# Controlador_de_velocidad.net
KiCad netlist of a schematic drawn in Altium Designer
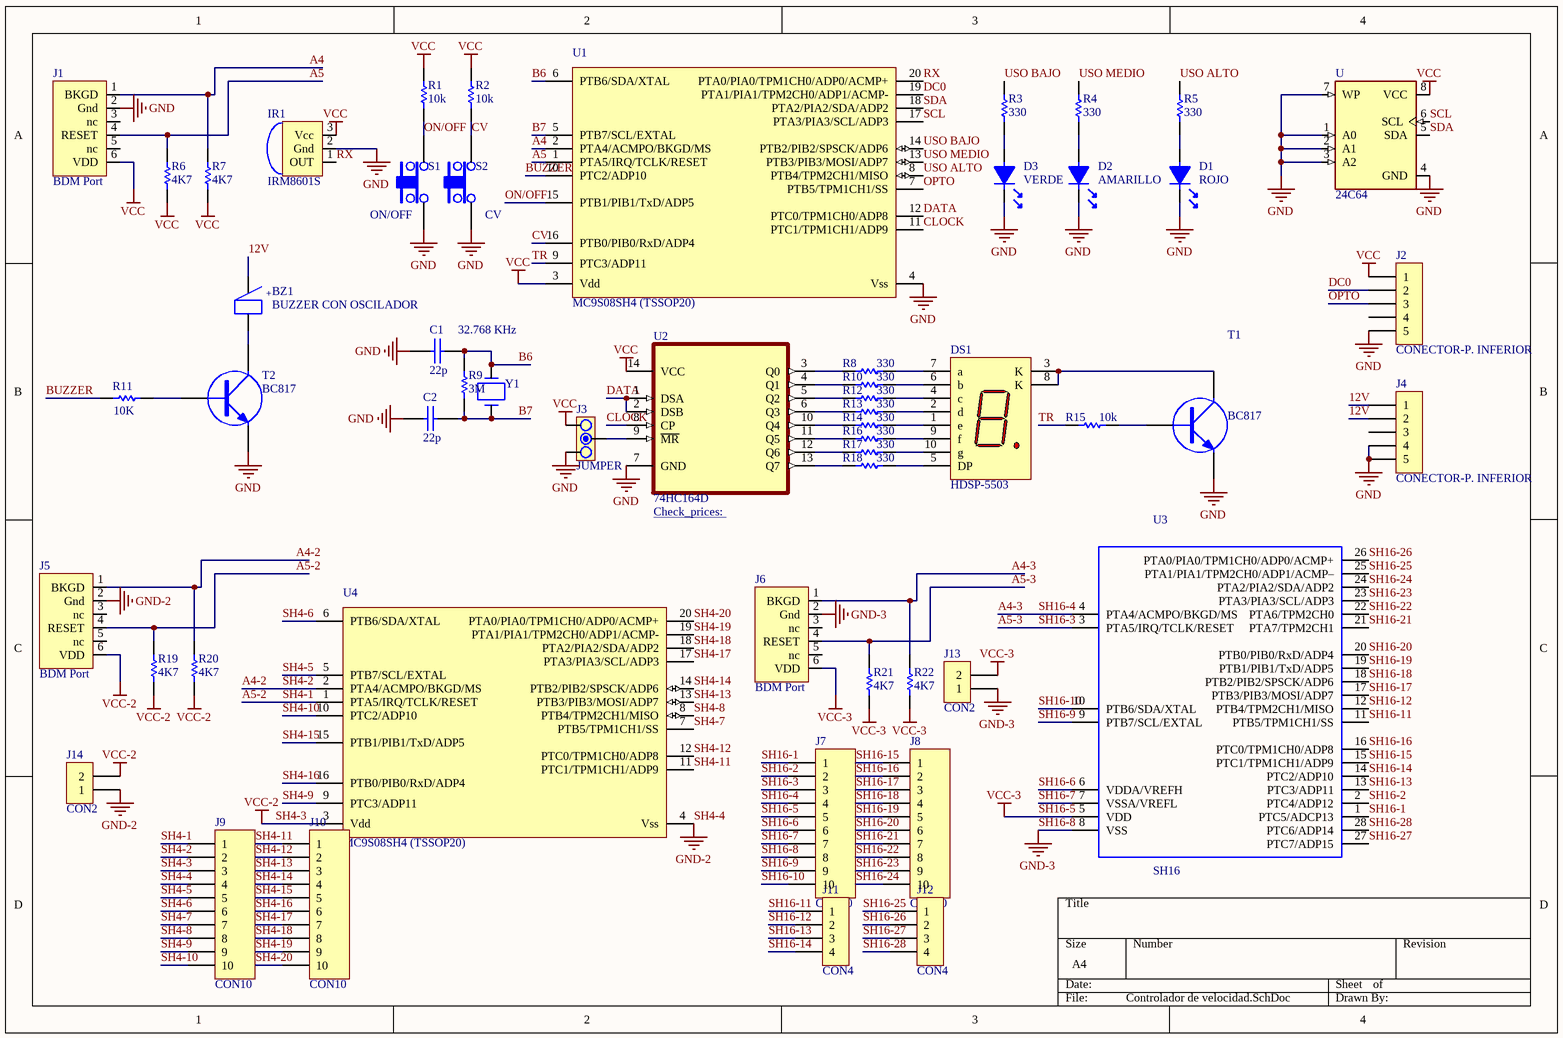
[diagram p0: Controlador de velocidad.SchDoc]

(export (version "E")
  (design (tool "Eeschema 10.0.6"))
  (components
    (comp (ref "BZ1")
      (value "BUZZER CON OSCILADOR")
      (footprint "BUZZER 12MM")
      (libsource (lib "LIBEBAL") (part "BUZZER"))
    )
    (comp (ref "C1") (value "22p") (footprint "0805") (libsource (lib "LIBPIOIX") (part "CAP")))
    (comp (ref "C2") (value "22p") (footprint "0805") (libsource (lib "LIBPIOIX") (part "CAP")))
    (comp (ref "D1") (value "ROJO") (footprint "LED5") (libsource (lib "LIBPIOIX") (part "LED")))
    (comp (ref "D2") (value "AMARILLO") (footprint "LED5") (libsource (lib "LIBPIOIX") (part "LED")))
    (comp (ref "D3") (value "VERDE") (footprint "LED5") (libsource (lib "LIBPIOIX") (part "LED")))
    (comp (ref "DS1")
      (value "HDSP-5503")
      (footprint "H-10")
      (description "14.22 mm Gray Surface HER 7-Segment Display: CC, RH DP")
      (fields (field (name "PUBLISHER") "Altium Limited"))
      (libsource (lib "Agilent LED Display 7-Segment, 1-Digit") (part "HDSP-5503"))
    )
    (comp (ref "IR1")
      (value "IRM8601S")
      (footprint "IRM8601S")
      (description "Sensor IR")
      (libsource (lib "*") (part "IRM8601S"))
    )
    (comp (ref "J1") (value "BDM Port") (footprint "JBDM") (libsource (lib "*") (part "JBDM")))
    (comp (ref "J2")
      (value "CONECTOR-P. INFERIOR")
      (footprint "SIP5")
      (libsource (lib "LIBEBAL") (part "CON5"))
    )
    (comp (ref "J3") (value "JUMPER") (footprint "JUMPER3") (libsource (lib "LIBPIOIX") (part "JUMPER3")))
    (comp (ref "J4")
      (value "CONECTOR-P. INFERIOR")
      (footprint "SIP5")
      (libsource (lib "LIBEBAL") (part "CON5"))
    )
    (comp (ref "J5") (value "BDM Port") (footprint "JBDM") (libsource (lib "*") (part "JBDM")))
    (comp (ref "J6") (value "BDM Port") (footprint "JBDM") (libsource (lib "*") (part "JBDM")))
    (comp (ref "J7") (value "CON10") (footprint "SIP10") (libsource (lib "LIBPIOIX") (part "CON10")))
    (comp (ref "J8") (value "CON10") (footprint "SIP10") (libsource (lib "LIBPIOIX") (part "CON10")))
    (comp (ref "J9") (value "CON10") (footprint "SIP10") (libsource (lib "LIBPIOIX") (part "CON10")))
    (comp (ref "J10") (value "CON10") (footprint "SIP10") (libsource (lib "LIBPIOIX") (part "CON10")))
    (comp (ref "J11") (value "CON4") (footprint "SIP4") (libsource (lib "LIBPIOIX") (part "CON4")))
    (comp (ref "J12") (value "CON4") (footprint "SIP4") (libsource (lib "LIBPIOIX") (part "CON4")))
    (comp (ref "J13") (value "CON2") (footprint "SIP2") (libsource (lib "LIBPIOIX") (part "CON2")))
    (comp (ref "J14") (value "CON2") (footprint "SIP2") (libsource (lib "LIBPIOIX") (part "CON2")))
    (comp (ref "R1") (value "10k") (footprint "0805") (libsource (lib "LIBPIOIX") (part "RES")))
    (comp (ref "R2") (value "10k") (footprint "0805") (libsource (lib "LIBPIOIX") (part "RES")))
    (comp (ref "R3") (value "330") (footprint "0805") (libsource (lib "LIBPIOIX") (part "RES")))
    (comp (ref "R4") (value "330") (footprint "0805") (libsource (lib "LIBPIOIX") (part "RES")))
    (comp (ref "R5") (value "330") (footprint "0805") (libsource (lib "LIBPIOIX") (part "RES")))
    (comp (ref "R6") (value "4K7") (footprint "0805") (libsource (lib "LIBPIOIX") (part "RES")))
    (comp (ref "R7") (value "4K7") (footprint "0805") (libsource (lib "LIBPIOIX") (part "RES")))
    (comp (ref "R8") (value "330") (footprint "0805") (libsource (lib "LIB PIO IX") (part "RES")))
    (comp (ref "R9") (value "3M") (footprint "0805") (libsource (lib "LIB PIO IX") (part "RES")))
    (comp (ref "R10") (value "330") (footprint "0805") (libsource (lib "LIB PIO IX") (part "RES")))
    (comp (ref "R11") (value "10K") (footprint "0805") (libsource (lib "LIBPIOIX") (part "RES")))
    (comp (ref "R12") (value "330") (footprint "0805") (libsource (lib "LIB PIO IX") (part "RES")))
    (comp (ref "R13") (value "330") (footprint "0805") (libsource (lib "LIB PIO IX") (part "RES")))
    (comp (ref "R14") (value "330") (footprint "0805") (libsource (lib "LIB PIO IX") (part "RES")))
    (comp (ref "R15") (value "10k") (footprint "0805") (libsource (lib "LIB PIO IX") (part "RES")))
    (comp (ref "R16") (value "330") (footprint "0805") (libsource (lib "LIB PIO IX") (part "RES")))
    (comp (ref "R17") (value "330") (footprint "0805") (libsource (lib "LIB PIO IX") (part "RES")))
    (comp (ref "R18") (value "330") (footprint "0805") (libsource (lib "LIB PIO IX") (part "RES")))
    (comp (ref "R19") (value "4K7") (footprint "0805") (libsource (lib "LIBPIOIX") (part "RES")))
    (comp (ref "R20") (value "4K7") (footprint "0805") (libsource (lib "LIBPIOIX") (part "RES")))
    (comp (ref "R21") (value "4K7") (footprint "0805") (libsource (lib "LIBPIOIX") (part "RES")))
    (comp (ref "R22") (value "4K7") (footprint "0805") (libsource (lib "LIBPIOIX") (part "RES")))
    (comp (ref "S1")
      (value "ON/OFF")
      (footprint "TACTSWITCH")
      (libsource (lib "LIBPIOIX") (part "TACT SWITCH"))
    )
    (comp (ref "S2") (value "CV") (footprint "TACTSWITCH") (libsource (lib "LIBPIOIX") (part "TACT SWITCH")))
    (comp (ref "T1") (value "BC817") (footprint "SOT23") (libsource (lib "LIBPIOIX") (part "TRANSISTOR NPN")))
    (comp (ref "T2") (value "BC817") (footprint "SOT23") (libsource (lib "LIBPIOIX") (part "TRANSISTOR NPN")))
    (comp (ref "U")
      (value "24C64")
      (footprint "SOIC127P600X175-8N")
      (description "EEPROM Memory IC 256Kb _32K x 8_ IÂ²C 1MHz 550ns 8-SOIC")
      (fields
        (field (name "MP") "AT24C256C-SSHL-T")
        (field (name "DIGI-KEY_PART_NUMBER") "AT24C256C-SSHL-TCT-ND")
      )
      (libsource (lib "AT24C256C-SSHL-T") (part "AT24C256C-SSHL-T"))
    )
    (comp (ref "U1")
      (value "MC9S08SH4 (TSSOP20)")
      (footprint "TSSOP20")
      (libsource (lib "*") (part "MC9S08SH8_20"))
    )
    (comp (ref "U2")
      (value "74HC164D")
      (footprint "SOIC127P600X175-14N")
      (description "Shift Shift Register 1 Element 8 Bit 14-SO")
      (fields (field (name "MF") "Nexperia USA") (field (name "MP") "74HC164D,653"))
      (libsource (lib "74HC164D_653") (part "74HC164D,653"))
    )
    (comp (ref "U3")
      (value "SH16")
      (footprint "*SOIC127P1032X265-28N")
      (description "3/5 Transceiver Full RS232 28-SOIC")
      (fields (field (name "MP") "MAX3243EWI") (field (name "MF") "Maxim Integrated"))
      (libsource (lib "MAX3243EWIT") (part "MAX3243EWIT"))
    )
    (comp (ref "U4")
      (value "MC9S08SH4 (TSSOP20)")
      (footprint "TSSOP20")
      (libsource (lib "*") (part "MC9S08SH8_20"))
    )
    (comp (ref "Y1") (value "32.768 KHz") (footprint "X32768") (libsource (lib "*") (part "CRYSTAL")))
  )
  (nets
    (net (code "1") (name "/12V") (class "Default")
      (node (ref "BZ1") (pin "1") (pinfunction "1_1") (pintype "passive"))
      (node (ref "J4") (pin "1") (pinfunction "1_1") (pintype "passive"))
      (node (ref "J4") (pin "2") (pinfunction "2_2") (pintype "passive"))
    )
    (net (code "2") (name "/A4") (class "Default")
      (node (ref "J1") (pin "1") (pinfunction "BKGD_1") (pintype "passive"))
      (node (ref "R7") (pin "2") (pinfunction "2_2") (pintype "passive"))
      (node (ref "U1") (pin "2") (pinfunction "PTA4/ACMPO/BKGD/MS_2") (pintype "passive"))
    )
    (net (code "3") (name "/A4-2") (class "Default")
      (node (ref "J5") (pin "1") (pinfunction "BKGD_1") (pintype "passive"))
      (node (ref "J9") (pin "2") (pinfunction "2_2") (pintype "passive"))
      (node (ref "R20") (pin "2") (pinfunction "2_2") (pintype "passive"))
      (node (ref "U4") (pin "2") (pinfunction "PTA4/ACMPO/BKGD/MS_2") (pintype "passive"))
    )
    (net (code "4") (name "/A4-3") (class "Default")
      (node (ref "J6") (pin "1") (pinfunction "BKGD_1") (pintype "passive"))
      (node (ref "J7") (pin "4") (pinfunction "4_4") (pintype "passive"))
      (node (ref "R22") (pin "2") (pinfunction "2_2") (pintype "passive"))
      (node (ref "U3") (pin "4") (pinfunction "PTA4/ACMPO/BKGD/MS_4") (pintype "passive"))
    )
    (net (code "5") (name "/A5") (class "Default")
      (node (ref "J1") (pin "4") (pinfunction "RESET_4") (pintype "passive"))
      (node (ref "R6") (pin "2") (pinfunction "2_2") (pintype "passive"))
      (node (ref "U1") (pin "1") (pinfunction "PTA5/IRQ/TCLK/RESET_1") (pintype "passive"))
    )
    (net (code "6") (name "/A5-2") (class "Default")
      (node (ref "J5") (pin "4") (pinfunction "RESET_4") (pintype "passive"))
      (node (ref "J9") (pin "1") (pinfunction "1_1") (pintype "passive"))
      (node (ref "R19") (pin "2") (pinfunction "2_2") (pintype "passive"))
      (node (ref "U4") (pin "1") (pinfunction "PTA5/IRQ/TCLK/RESET_1") (pintype "passive"))
    )
    (net (code "7") (name "/A5-3") (class "Default")
      (node (ref "J6") (pin "4") (pinfunction "RESET_4") (pintype "passive"))
      (node (ref "J7") (pin "3") (pinfunction "3_3") (pintype "passive"))
      (node (ref "R21") (pin "2") (pinfunction "2_2") (pintype "passive"))
      (node (ref "U3") (pin "3") (pinfunction "PTA5/IRQ/TCLK/RESET_3") (pintype "passive"))
    )
    (net (code "8") (name "/B6") (class "Default")
      (node (ref "C1") (pin "1") (pinfunction "1_1") (pintype "passive"))
      (node (ref "R9") (pin "2") (pinfunction "2_2") (pintype "passive"))
      (node (ref "U1") (pin "6") (pinfunction "PTB6/SDA/XTAL_6") (pintype "passive"))
      (node (ref "Y1") (pin "2") (pinfunction "2_2") (pintype "passive"))
    )
    (net (code "9") (name "/B7") (class "Default")
      (node (ref "C2") (pin "1") (pinfunction "1_1") (pintype "passive"))
      (node (ref "R9") (pin "1") (pinfunction "1_1") (pintype "passive"))
      (node (ref "U1") (pin "5") (pinfunction "PTB7/SCL/EXTAL_5") (pintype "passive"))
      (node (ref "Y1") (pin "1") (pinfunction "1_1") (pintype "passive"))
    )
    (net (code "10") (name "/BUZZER") (class "Default")
      (node (ref "R11") (pin "1") (pinfunction "1_1") (pintype "passive"))
      (node (ref "U1") (pin "10") (pinfunction "PTC2/ADP10_10") (pintype "passive"))
    )
    (net (code "11") (name "/CLOCK") (class "Default")
      (node (ref "U1") (pin "11") (pinfunction "PTC1/TPM1CH1/ADP9_11") (pintype "passive"))
      (node (ref "U2") (pin "8") (pinfunction "CP_8") (pintype "input"))
    )
    (net (code "12") (name "/CV") (class "Default")
      (node (ref "R2") (pin "1") (pinfunction "1_1") (pintype "passive"))
      (node (ref "S2") (pin "2") (pinfunction "2_2") (pintype "passive"))
      (node (ref "U1") (pin "16") (pinfunction "PTB0/PIB0/RxD/ADP4_16") (pintype "passive"))
    )
    (net (code "13") (name "/DATA") (class "Default")
      (node (ref "U1") (pin "12") (pinfunction "PTC0/TPM1CH0/ADP8_12") (pintype "passive"))
      (node (ref "U2") (pin "1") (pinfunction "DSA_1") (pintype "input"))
      (node (ref "U2") (pin "2") (pinfunction "DSB_2") (pintype "input"))
    )
    (net (code "14") (name "/DC0") (class "Default")
      (node (ref "J2") (pin "2") (pinfunction "2_2") (pintype "passive"))
      (node (ref "U1") (pin "19") (pinfunction "PTA1/PIA1/TPM2CH0/ADP1/ACMP-_19") (pintype "passive"))
    )
    (net (code "15") (name "/ON{slash}OFF") (class "Default")
      (node (ref "R1") (pin "1") (pinfunction "1_1") (pintype "passive"))
      (node (ref "S1") (pin "2") (pinfunction "2_2") (pintype "passive"))
      (node (ref "U1") (pin "15") (pinfunction "PTB1/PIB1/TxD/ADP5_15") (pintype "passive"))
    )
    (net (code "16") (name "/OPTO") (class "Default")
      (node (ref "J2") (pin "3") (pinfunction "3_3") (pintype "passive"))
      (node (ref "U1") (pin "7") (pinfunction "PTB5/TPM1CH1/SS_7") (pintype "passive"))
    )
    (net (code "17") (name "/RX") (class "Default")
      (node (ref "IR1") (pin "1") (pinfunction "OUT_1") (pintype "passive"))
      (node (ref "U1") (pin "20") (pinfunction "PTA0/PIA0/TPM1CH0/ADP0/ACMP+_20") (pintype "passive"))
    )
    (net (code "18") (name "/SCL") (class "Default")
      (node (ref "U") (pin "6") (pinfunction "SCL_6") (pintype "input"))
      (node (ref "U1") (pin "17") (pinfunction "PTA3/PIA3/SCL/ADP3_17") (pintype "passive"))
    )
    (net (code "19") (name "/SDA") (class "Default")
      (node (ref "U") (pin "5") (pinfunction "SDA_5") (pintype "bidirectional"))
      (node (ref "U1") (pin "18") (pinfunction "PTA2/PIA2/SDA/ADP2_18") (pintype "passive"))
    )
    (net (code "20") (name "/SH4-5") (class "Default")
      (node (ref "J9") (pin "5") (pinfunction "5_5") (pintype "passive"))
      (node (ref "U4") (pin "5") (pinfunction "PTB7/SCL/EXTAL_5") (pintype "passive"))
    )
    (net (code "21") (name "/SH4-6") (class "Default")
      (node (ref "J9") (pin "6") (pinfunction "6_6") (pintype "passive"))
      (node (ref "U4") (pin "6") (pinfunction "PTB6/SDA/XTAL_6") (pintype "passive"))
    )
    (net (code "22") (name "/SH4-7") (class "Default")
      (node (ref "J9") (pin "7") (pinfunction "7_7") (pintype "passive"))
      (node (ref "U4") (pin "7") (pinfunction "PTB5/TPM1CH1/SS_7") (pintype "passive"))
    )
    (net (code "23") (name "/SH4-8") (class "Default")
      (node (ref "J9") (pin "8") (pinfunction "8_8") (pintype "passive"))
      (node (ref "U4") (pin "8") (pinfunction "PTB4/TPM2CH1/MISO_8") (pintype "bidirectional"))
    )
    (net (code "24") (name "/SH4-9") (class "Default")
      (node (ref "J9") (pin "9") (pinfunction "9_9") (pintype "passive"))
      (node (ref "U4") (pin "9") (pinfunction "PTC3/ADP11_9") (pintype "passive"))
    )
    (net (code "25") (name "/SH4-10") (class "Default")
      (node (ref "J9") (pin "10") (pinfunction "10_10") (pintype "passive"))
      (node (ref "U4") (pin "10") (pinfunction "PTC2/ADP10_10") (pintype "passive"))
    )
    (net (code "26") (name "/SH4-11") (class "Default")
      (node (ref "J10") (pin "1") (pinfunction "1_1") (pintype "passive"))
      (node (ref "U4") (pin "11") (pinfunction "PTC1/TPM1CH1/ADP9_11") (pintype "passive"))
    )
    (net (code "27") (name "/SH4-12") (class "Default")
      (node (ref "J10") (pin "2") (pinfunction "2_2") (pintype "passive"))
      (node (ref "U4") (pin "12") (pinfunction "PTC0/TPM1CH0/ADP8_12") (pintype "passive"))
    )
    (net (code "28") (name "/SH4-13") (class "Default")
      (node (ref "J10") (pin "3") (pinfunction "3_3") (pintype "passive"))
      (node (ref "U4") (pin "13") (pinfunction "PTB3/PIB3/MOSI/ADP7_13") (pintype "bidirectional"))
    )
    (net (code "29") (name "/SH4-14") (class "Default")
      (node (ref "J10") (pin "4") (pinfunction "4_4") (pintype "passive"))
      (node (ref "U4") (pin "14") (pinfunction "PTB2/PIB2/SPSCK/ADP6_14") (pintype "bidirectional"))
    )
    (net (code "30") (name "/SH4-15") (class "Default")
      (node (ref "J10") (pin "5") (pinfunction "5_5") (pintype "passive"))
      (node (ref "U4") (pin "15") (pinfunction "PTB1/PIB1/TxD/ADP5_15") (pintype "passive"))
    )
    (net (code "31") (name "/SH4-16") (class "Default")
      (node (ref "J10") (pin "6") (pinfunction "6_6") (pintype "passive"))
      (node (ref "U4") (pin "16") (pinfunction "PTB0/PIB0/RxD/ADP4_16") (pintype "passive"))
    )
    (net (code "32") (name "/SH4-17") (class "Default")
      (node (ref "J10") (pin "7") (pinfunction "7_7") (pintype "passive"))
      (node (ref "U4") (pin "17") (pinfunction "PTA3/PIA3/SCL/ADP3_17") (pintype "passive"))
    )
    (net (code "33") (name "/SH4-18") (class "Default")
      (node (ref "J10") (pin "8") (pinfunction "8_8") (pintype "passive"))
      (node (ref "U4") (pin "18") (pinfunction "PTA2/PIA2/SDA/ADP2_18") (pintype "passive"))
    )
    (net (code "34") (name "/SH4-19") (class "Default")
      (node (ref "J10") (pin "9") (pinfunction "9_9") (pintype "passive"))
      (node (ref "U4") (pin "19") (pinfunction "PTA1/PIA1/TPM2CH0/ADP1/ACMP-_19") (pintype "passive"))
    )
    (net (code "35") (name "/SH4-20") (class "Default")
      (node (ref "J10") (pin "10") (pinfunction "10_10") (pintype "passive"))
      (node (ref "U4") (pin "20") (pinfunction "PTA0/PIA0/TPM1CH0/ADP0/ACMP+_20") (pintype "passive"))
    )
    (net (code "36") (name "/SH16-1") (class "Default")
      (node (ref "J7") (pin "1") (pinfunction "1_1") (pintype "passive"))
      (node (ref "U3") (pin "1") (pinfunction "PTC5/ADCP13_1") (pintype "passive"))
    )
    (net (code "37") (name "/SH16-2") (class "Default")
      (node (ref "J7") (pin "2") (pinfunction "2_2") (pintype "passive"))
      (node (ref "U3") (pin "2") (pinfunction "PTC4/ADP12_2") (pintype "passive"))
    )
    (net (code "38") (name "/SH16-6") (class "Default")
      (node (ref "J7") (pin "6") (pinfunction "6_6") (pintype "passive"))
      (node (ref "U3") (pin "6") (pinfunction "VDDA/VREFH_6") (pintype "passive"))
    )
    (net (code "39") (name "/SH16-7") (class "Default")
      (node (ref "J7") (pin "7") (pinfunction "7_7") (pintype "passive"))
      (node (ref "U3") (pin "7") (pinfunction "VSSA/VREFL_7") (pintype "passive"))
    )
    (net (code "40") (name "/SH16-9") (class "Default")
      (node (ref "J7") (pin "9") (pinfunction "9_9") (pintype "passive"))
      (node (ref "U3") (pin "9") (pinfunction "PTB7/SCL/EXTAL_9") (pintype "passive"))
    )
    (net (code "41") (name "/SH16-10") (class "Default")
      (node (ref "J7") (pin "10") (pinfunction "10_10") (pintype "passive"))
      (node (ref "U3") (pin "10") (pinfunction "PTB6/SDA/XTAL_10") (pintype "passive"))
    )
    (net (code "42") (name "/SH16-11") (class "Default")
      (node (ref "J11") (pin "1") (pinfunction "1_1") (pintype "passive"))
      (node (ref "U3") (pin "11") (pinfunction "PTB5/TPM1CH1/SS_11") (pintype "passive"))
    )
    (net (code "43") (name "/SH16-12") (class "Default")
      (node (ref "J11") (pin "2") (pinfunction "2_2") (pintype "passive"))
      (node (ref "U3") (pin "12") (pinfunction "PTB4/TPM2CH1/MISO_12") (pintype "passive"))
    )
    (net (code "44") (name "/SH16-13") (class "Default")
      (node (ref "J11") (pin "3") (pinfunction "3_3") (pintype "passive"))
      (node (ref "U3") (pin "13") (pinfunction "PTC3/ADP11_13") (pintype "passive"))
    )
    (net (code "45") (name "/SH16-14") (class "Default")
      (node (ref "J11") (pin "4") (pinfunction "4_4") (pintype "passive"))
      (node (ref "U3") (pin "14") (pinfunction "PTC2/ADP10_14") (pintype "passive"))
    )
    (net (code "46") (name "/SH16-15") (class "Default")
      (node (ref "J8") (pin "1") (pinfunction "1_1") (pintype "passive"))
      (node (ref "U3") (pin "15") (pinfunction "PTC1/TPM1CH1/ADP9_15") (pintype "passive"))
    )
    (net (code "47") (name "/SH16-16") (class "Default")
      (node (ref "J8") (pin "2") (pinfunction "2_2") (pintype "passive"))
      (node (ref "U3") (pin "16") (pinfunction "PTC0/TPM1CH0/ADP8_16") (pintype "passive"))
    )
    (net (code "48") (name "/SH16-17") (class "Default")
      (node (ref "J8") (pin "3") (pinfunction "3_3") (pintype "passive"))
      (node (ref "U3") (pin "17") (pinfunction "PTB3/PIB3/MOSI/ADP7_17") (pintype "passive"))
    )
    (net (code "49") (name "/SH16-18") (class "Default")
      (node (ref "J8") (pin "4") (pinfunction "4_4") (pintype "passive"))
      (node (ref "U3") (pin "18") (pinfunction "PTB2/PIB2/SPSCK/ADP6_18") (pintype "passive"))
    )
    (net (code "50") (name "/SH16-19") (class "Default")
      (node (ref "J8") (pin "5") (pinfunction "5_5") (pintype "passive"))
      (node (ref "U3") (pin "19") (pinfunction "PTB1/PIB1/TxD/ADP5_19") (pintype "passive"))
    )
    (net (code "51") (name "/SH16-20") (class "Default")
      (node (ref "J8") (pin "6") (pinfunction "6_6") (pintype "passive"))
      (node (ref "U3") (pin "20") (pinfunction "PTB0/PIB0/RxD/ADP4_20") (pintype "passive"))
    )
    (net (code "52") (name "/SH16-21") (class "Default")
      (node (ref "J8") (pin "7") (pinfunction "7_7") (pintype "passive"))
      (node (ref "U3") (pin "21") (pinfunction "PTA7/TPM2CH1_21") (pintype "passive"))
    )
    (net (code "53") (name "/SH16-22") (class "Default")
      (node (ref "J8") (pin "8") (pinfunction "8_8") (pintype "passive"))
      (node (ref "U3") (pin "22") (pinfunction "PTA6/TPM2CH0_22") (pintype "passive"))
    )
    (net (code "54") (name "/SH16-23") (class "Default")
      (node (ref "J8") (pin "9") (pinfunction "9_9") (pintype "passive"))
      (node (ref "U3") (pin "23") (pinfunction "PTA3/PIA3/SCL/ADP3_23") (pintype "passive"))
    )
    (net (code "55") (name "/SH16-24") (class "Default")
      (node (ref "J8") (pin "10") (pinfunction "10_10") (pintype "passive"))
      (node (ref "U3") (pin "24") (pinfunction "PTA2/PIA2/SDA/ADP2_24") (pintype "passive"))
    )
    (net (code "56") (name "/SH16-25") (class "Default")
      (node (ref "J12") (pin "1") (pinfunction "1_1") (pintype "passive"))
      (node (ref "U3") (pin "25") (pinfunction "PTA1/PIA1/TPM2CH0/ADP1/ACMP–_25") (pintype "passive"))
    )
    (net (code "57") (name "/SH16-26") (class "Default")
      (node (ref "J12") (pin "2") (pinfunction "2_2") (pintype "passive"))
      (node (ref "U3") (pin "26") (pinfunction "PTA0/PIA0/TPM1CH0/ADP0/ACMP+_26") (pintype "passive"))
    )
    (net (code "58") (name "/SH16-27") (class "Default")
      (node (ref "J12") (pin "3") (pinfunction "3_3") (pintype "passive"))
      (node (ref "U3") (pin "27") (pinfunction "PTC7/ADP15_27") (pintype "passive"))
    )
    (net (code "59") (name "/SH16-28") (class "Default")
      (node (ref "J12") (pin "4") (pinfunction "4_4") (pintype "passive"))
      (node (ref "U3") (pin "28") (pinfunction "PTC6/ADP14_28") (pintype "passive"))
    )
    (net (code "60") (name "/TR") (class "Default")
      (node (ref "R15") (pin "1") (pinfunction "1_1") (pintype "passive"))
      (node (ref "U1") (pin "9") (pinfunction "PTC3/ADP11_9") (pintype "passive"))
    )
    (net (code "61") (name "/USO ALTO") (class "Default")
      (node (ref "R5") (pin "2") (pinfunction "2_2") (pintype "passive"))
      (node (ref "U1") (pin "8") (pinfunction "PTB4/TPM2CH1/MISO_8") (pintype "bidirectional"))
    )
    (net (code "62") (name "/USO BAJO") (class "Default")
      (node (ref "R3") (pin "2") (pinfunction "2_2") (pintype "passive"))
      (node (ref "U1") (pin "14") (pinfunction "PTB2/PIB2/SPSCK/ADP6_14") (pintype "bidirectional"))
    )
    (net (code "63") (name "/USO MEDIO") (class "Default")
      (node (ref "R4") (pin "2") (pinfunction "2_2") (pintype "passive"))
      (node (ref "U1") (pin "13") (pinfunction "PTB3/PIB3/MOSI/ADP7_13") (pintype "bidirectional"))
    )
    (net (code "64") (name "GND") (class "Default")
      (node (ref "C1") (pin "2") (pinfunction "2_2") (pintype "passive"))
      (node (ref "C2") (pin "2") (pinfunction "2_2") (pintype "passive"))
      (node (ref "D1") (pin "2") (pinfunction "2_2") (pintype "passive"))
      (node (ref "D2") (pin "2") (pinfunction "2_2") (pintype "passive"))
      (node (ref "D3") (pin "2") (pinfunction "2_2") (pintype "passive"))
      (node (ref "IR1") (pin "2") (pinfunction "Gnd_2") (pintype "passive"))
      (node (ref "J1") (pin "2") (pinfunction "Gnd_2") (pintype "passive"))
      (node (ref "J2") (pin "5") (pinfunction "5_5") (pintype "passive"))
      (node (ref "J3") (pin "1") (pinfunction "1_1") (pintype "passive"))
      (node (ref "J4") (pin "4") (pinfunction "4_4") (pintype "passive"))
      (node (ref "J4") (pin "5") (pinfunction "5_5") (pintype "passive"))
      (node (ref "S1") (pin "1") (pinfunction "1_1") (pintype "passive"))
      (node (ref "S2") (pin "1") (pinfunction "1_1") (pintype "passive"))
      (node (ref "T1") (pin "3") (pinfunction "E_3") (pintype "passive"))
      (node (ref "T2") (pin "3") (pinfunction "E_3") (pintype "passive"))
      (node (ref "U") (pin "1") (pinfunction "A0_1") (pintype "input"))
      (node (ref "U") (pin "2") (pinfunction "A1_2") (pintype "input"))
      (node (ref "U") (pin "3") (pinfunction "A2_3") (pintype "input"))
      (node (ref "U") (pin "4") (pinfunction "GND_4") (pintype "power_in"))
      (node (ref "U") (pin "7") (pinfunction "WP_7") (pintype "input"))
      (node (ref "U1") (pin "4") (pinfunction "Vss_4") (pintype "passive"))
      (node (ref "U2") (pin "7") (pinfunction "GND_7") (pintype "passive"))
    )
    (net (code "65") (name "GND-2") (class "Default")
      (node (ref "J14") (pin "1") (pinfunction "1_1") (pintype "passive"))
      (node (ref "J5") (pin "2") (pinfunction "Gnd_2") (pintype "passive"))
      (node (ref "J9") (pin "4") (pinfunction "4_4") (pintype "passive"))
      (node (ref "U4") (pin "4") (pinfunction "Vss_4") (pintype "passive"))
    )
    (net (code "66") (name "GND-3") (class "Default")
      (node (ref "J13") (pin "1") (pinfunction "1_1") (pintype "passive"))
      (node (ref "J6") (pin "2") (pinfunction "Gnd_2") (pintype "passive"))
      (node (ref "J7") (pin "8") (pinfunction "8_8") (pintype "passive"))
      (node (ref "U3") (pin "8") (pinfunction "VSS_8") (pintype "passive"))
    )
    (net (code "67") (name "Net-(D1-Pad1)") (class "Default")
      (node (ref "D1") (pin "1") (pinfunction "1_1") (pintype "passive"))
      (node (ref "R5") (pin "1") (pinfunction "1_1") (pintype "passive"))
    )
    (net (code "68") (name "Net-(D2-Pad1)") (class "Default")
      (node (ref "D2") (pin "1") (pinfunction "1_1") (pintype "passive"))
      (node (ref "R4") (pin "1") (pinfunction "1_1") (pintype "passive"))
    )
    (net (code "69") (name "Net-(D3-Pad1)") (class "Default")
      (node (ref "D3") (pin "1") (pinfunction "1_1") (pintype "passive"))
      (node (ref "R3") (pin "1") (pinfunction "1_1") (pintype "passive"))
    )
    (net (code "70") (name "Net-(DS1-DP)") (class "Default")
      (node (ref "DS1") (pin "5") (pinfunction "DP_5") (pintype "passive"))
      (node (ref "R18") (pin "2") (pinfunction "2_2") (pintype "passive"))
    )
    (net (code "71") (name "Net-(DS1-a)") (class "Default")
      (node (ref "DS1") (pin "7") (pinfunction "a_7") (pintype "passive"))
      (node (ref "R8") (pin "2") (pinfunction "2_2") (pintype "passive"))
    )
    (net (code "72") (name "Net-(DS1-b)") (class "Default")
      (node (ref "DS1") (pin "6") (pinfunction "b_6") (pintype "passive"))
      (node (ref "R10") (pin "2") (pinfunction "2_2") (pintype "passive"))
    )
    (net (code "73") (name "Net-(DS1-c)") (class "Default")
      (node (ref "DS1") (pin "4") (pinfunction "c_4") (pintype "passive"))
      (node (ref "R12") (pin "2") (pinfunction "2_2") (pintype "passive"))
    )
    (net (code "74") (name "Net-(DS1-d)") (class "Default")
      (node (ref "DS1") (pin "2") (pinfunction "d_2") (pintype "passive"))
      (node (ref "R13") (pin "2") (pinfunction "2_2") (pintype "passive"))
    )
    (net (code "75") (name "Net-(DS1-e)") (class "Default")
      (node (ref "DS1") (pin "1") (pinfunction "e_1") (pintype "passive"))
      (node (ref "R14") (pin "2") (pinfunction "2_2") (pintype "passive"))
    )
    (net (code "76") (name "Net-(DS1-f)") (class "Default")
      (node (ref "DS1") (pin "9") (pinfunction "f_9") (pintype "passive"))
      (node (ref "R16") (pin "2") (pinfunction "2_2") (pintype "passive"))
    )
    (net (code "77") (name "Net-(DS1-g)") (class "Default")
      (node (ref "DS1") (pin "10") (pinfunction "g_10") (pintype "passive"))
      (node (ref "R17") (pin "2") (pinfunction "2_2") (pintype "passive"))
    )
    (net (code "78") (name "Net-(T1-B)") (class "Default")
      (node (ref "R15") (pin "2") (pinfunction "2_2") (pintype "passive"))
      (node (ref "T1") (pin "1") (pinfunction "B_1") (pintype "passive"))
    )
    (net (code "79") (name "Net-(T1-C)") (class "Default")
      (node (ref "DS1") (pin "3") (pinfunction "K_3") (pintype "passive"))
      (node (ref "DS1") (pin "8") (pinfunction "K_8") (pintype "passive"))
      (node (ref "T1") (pin "2") (pinfunction "C_2") (pintype "passive"))
    )
    (net (code "80") (name "Net-(T2-B)") (class "Default")
      (node (ref "R11") (pin "2") (pinfunction "2_2") (pintype "passive"))
      (node (ref "T2") (pin "1") (pinfunction "B_1") (pintype "passive"))
    )
    (net (code "81") (name "Net-(T2-C)") (class "Default")
      (node (ref "BZ1") (pin "2") (pinfunction "2_2") (pintype "passive"))
      (node (ref "T2") (pin "2") (pinfunction "C_2") (pintype "passive"))
    )
    (net (code "82") (name "Net-(U2-Q0)") (class "Default")
      (node (ref "R8") (pin "1") (pinfunction "1_1") (pintype "passive"))
      (node (ref "U2") (pin "3") (pinfunction "Q0_3") (pintype "output"))
    )
    (net (code "83") (name "Net-(U2-Q1)") (class "Default")
      (node (ref "R10") (pin "1") (pinfunction "1_1") (pintype "passive"))
      (node (ref "U2") (pin "4") (pinfunction "Q1_4") (pintype "output"))
    )
    (net (code "84") (name "Net-(U2-Q2)") (class "Default")
      (node (ref "R12") (pin "1") (pinfunction "1_1") (pintype "passive"))
      (node (ref "U2") (pin "5") (pinfunction "Q2_5") (pintype "output"))
    )
    (net (code "85") (name "Net-(U2-Q3)") (class "Default")
      (node (ref "R13") (pin "1") (pinfunction "1_1") (pintype "passive"))
      (node (ref "U2") (pin "6") (pinfunction "Q3_6") (pintype "output"))
    )
    (net (code "86") (name "Net-(U2-Q4)") (class "Default")
      (node (ref "R14") (pin "1") (pinfunction "1_1") (pintype "passive"))
      (node (ref "U2") (pin "10") (pinfunction "Q4_10") (pintype "output"))
    )
    (net (code "87") (name "Net-(U2-Q5)") (class "Default")
      (node (ref "R16") (pin "1") (pinfunction "1_1") (pintype "passive"))
      (node (ref "U2") (pin "11") (pinfunction "Q5_11") (pintype "output"))
    )
    (net (code "88") (name "Net-(U2-Q6)") (class "Default")
      (node (ref "R17") (pin "1") (pinfunction "1_1") (pintype "passive"))
      (node (ref "U2") (pin "12") (pinfunction "Q6_12") (pintype "output"))
    )
    (net (code "89") (name "Net-(U2-Q7)") (class "Default")
      (node (ref "R18") (pin "1") (pinfunction "1_1") (pintype "passive"))
      (node (ref "U2") (pin "13") (pinfunction "Q7_13") (pintype "output"))
    )
    (net (code "90") (name "Net-(U2-~{MR})") (class "Default")
      (node (ref "J3") (pin "2") (pinfunction "2_2") (pintype "passive"))
      (node (ref "U2") (pin "9") (pinfunction "~{MR}_9") (pintype "input"))
    )
    (net (code "91") (name "VCC") (class "Default")
      (node (ref "IR1") (pin "3") (pinfunction "Vcc_3") (pintype "passive"))
      (node (ref "J1") (pin "6") (pinfunction "VDD_6") (pintype "passive"))
      (node (ref "J2") (pin "1") (pinfunction "1_1") (pintype "passive"))
      (node (ref "J3") (pin "3") (pinfunction "3_3") (pintype "passive"))
      (node (ref "R1") (pin "2") (pinfunction "2_2") (pintype "passive"))
      (node (ref "R2") (pin "2") (pinfunction "2_2") (pintype "passive"))
      (node (ref "R6") (pin "1") (pinfunction "1_1") (pintype "passive"))
      (node (ref "R7") (pin "1") (pinfunction "1_1") (pintype "passive"))
      (node (ref "U") (pin "8") (pinfunction "VCC_8") (pintype "power_in"))
      (node (ref "U1") (pin "3") (pinfunction "Vdd_3") (pintype "passive"))
      (node (ref "U2") (pin "14") (pinfunction "VCC_14") (pintype "power_in"))
    )
    (net (code "92") (name "VCC-2") (class "Default")
      (node (ref "J14") (pin "2") (pinfunction "2_2") (pintype "passive"))
      (node (ref "J5") (pin "6") (pinfunction "VDD_6") (pintype "passive"))
      (node (ref "J9") (pin "3") (pinfunction "3_3") (pintype "passive"))
      (node (ref "R19") (pin "1") (pinfunction "1_1") (pintype "passive"))
      (node (ref "R20") (pin "1") (pinfunction "1_1") (pintype "passive"))
      (node (ref "U4") (pin "3") (pinfunction "Vdd_3") (pintype "passive"))
    )
    (net (code "93") (name "VCC-3") (class "Default")
      (node (ref "J13") (pin "2") (pinfunction "2_2") (pintype "passive"))
      (node (ref "J6") (pin "6") (pinfunction "VDD_6") (pintype "passive"))
      (node (ref "J7") (pin "5") (pinfunction "5_5") (pintype "passive"))
      (node (ref "R21") (pin "1") (pinfunction "1_1") (pintype "passive"))
      (node (ref "R22") (pin "1") (pinfunction "1_1") (pintype "passive"))
      (node (ref "U3") (pin "5") (pinfunction "VDD_5") (pintype "passive"))
    )
    (net (code "94") (name "unconnected-(J1-nc-Pad3)") (class "Default")
      (node (ref "J1") (pin "3") (pinfunction "nc_3") (pintype "passive"))
    )
    (net (code "95") (name "unconnected-(J1-nc-Pad5)") (class "Default")
      (node (ref "J1") (pin "5") (pinfunction "nc_5") (pintype "passive"))
    )
    (net (code "96") (name "unconnected-(J2-Pad4)") (class "Default")
      (node (ref "J2") (pin "4") (pinfunction "4_4") (pintype "passive"))
    )
    (net (code "97") (name "unconnected-(J4-Pad3)") (class "Default")
      (node (ref "J4") (pin "3") (pinfunction "3_3") (pintype "passive"))
    )
    (net (code "98") (name "unconnected-(J5-nc-Pad3)") (class "Default")
      (node (ref "J5") (pin "3") (pinfunction "nc_3") (pintype "passive"))
    )
    (net (code "99") (name "unconnected-(J5-nc-Pad5)") (class "Default")
      (node (ref "J5") (pin "5") (pinfunction "nc_5") (pintype "passive"))
    )
    (net (code "100") (name "unconnected-(J6-nc-Pad3)") (class "Default")
      (node (ref "J6") (pin "3") (pinfunction "nc_3") (pintype "passive"))
    )
    (net (code "101") (name "unconnected-(J6-nc-Pad5)") (class "Default")
      (node (ref "J6") (pin "5") (pinfunction "nc_5") (pintype "passive"))
    )
  )
)
